# Audio_Input_Digitial_Mic.net
KiCad netlist of a schematic drawn in Altium Designer
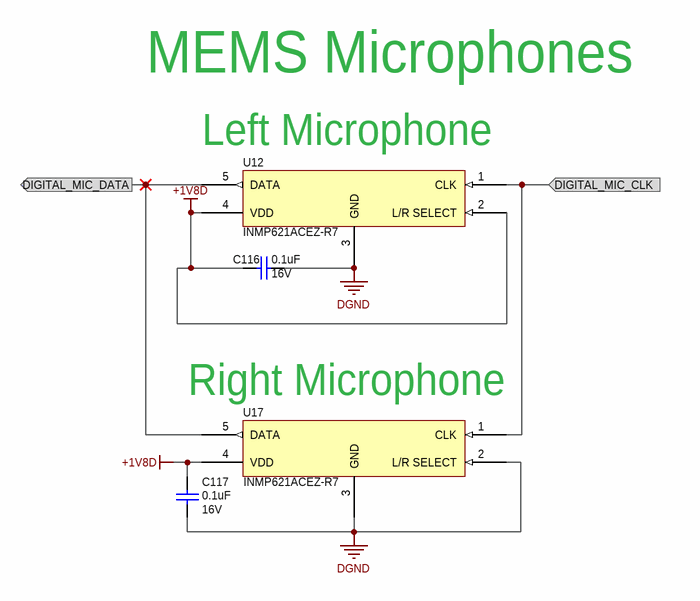
[diagram p0: Audio_Input_Digitial_Mic.SchDoc]

(export (version "E")
  (design (tool "Eeschema 10.0.6"))
  (components
    (comp (ref "C116")
      (value "CL10F104ZO8NNNC")
      (footprint "3-0603_L")
      (description "CAP CER 0.1UF 16V Y5V 0603")
      (fields
        (field (name "MANUFACTURER") "Samsung")
        (field (name "TOLERANCE") "80%")
        (field (name "VOLTAGE RATING") "16V")
        (field (name "CAPACITANCE") "0.1uF")
      )
      (libsource (lib "Schematic_Components_CD") (part "CL10F104ZO8NNNC"))
    )
    (comp (ref "C117")
      (value "CL10F104ZO8NNNC")
      (footprint "3-0603_L")
      (description "CAP CER 0.1UF 16V Y5V 0603")
      (fields
        (field (name "MANUFACTURER") "Samsung")
        (field (name "TOLERANCE") "80%")
        (field (name "VOLTAGE RATING") "16V")
        (field (name "CAPACITANCE") "0.1uF")
      )
      (libsource (lib "Schematic_Components_CD") (part "CL10F104ZO8NNNC"))
    )
    (comp (ref "U12")
      (value "INMP621")
      (footprint "INMP621")
      (fields
        (field (name "MANUFACTURER") "InvenSense")
        (field (name "MANUFACTURER PART NUMBER") "INMP621ACEZ-R7")
      )
      (libsource (lib "NIH_DE0_Nano_Daughter_Card_Library") (part "INMP621"))
    )
    (comp (ref "U17")
      (value "INMP621")
      (footprint "INMP621")
      (fields
        (field (name "MANUFACTURER") "InvenSense")
        (field (name "MANUFACTURER PART NUMBER") "INMP621ACEZ-R7")
      )
      (libsource (lib "NIH_DE0_Nano_Daughter_Card_Library") (part "INMP621"))
    )
  )
  (nets
    (net (code "1") (name "+1V8D") (class "Default")
      (node (ref "C116") (pin "2") (pinfunction "2_2") (pintype "passive"))
      (node (ref "C117") (pin "1") (pinfunction "1_1") (pintype "passive"))
      (node (ref "U12") (pin "2") (pinfunction "L/R_SELECT_2") (pintype "input"))
      (node (ref "U12") (pin "4") (pinfunction "VDD_4") (pintype "passive"))
      (node (ref "U17") (pin "4") (pinfunction "VDD_4") (pintype "passive"))
    )
    (net (code "2") (name "/DIGITAL_MIC_CLK") (class "Default")
      (node (ref "U12") (pin "1") (pinfunction "CLK_1") (pintype "input"))
      (node (ref "U17") (pin "1") (pinfunction "CLK_1") (pintype "input"))
    )
    (net (code "3") (name "/DIGITAL_MIC_DATA") (class "Default")
      (node (ref "U12") (pin "5") (pinfunction "DATA_5") (pintype "output"))
      (node (ref "U17") (pin "5") (pinfunction "DATA_5") (pintype "output"))
    )
    (net (code "4") (name "DGND") (class "Default")
      (node (ref "C116") (pin "1") (pinfunction "1_1") (pintype "passive"))
      (node (ref "C117") (pin "2") (pinfunction "2_2") (pintype "passive"))
      (node (ref "U12") (pin "3") (pinfunction "GND_3") (pintype "passive"))
      (node (ref "U17") (pin "2") (pinfunction "L/R_SELECT_2") (pintype "input"))
      (node (ref "U17") (pin "3") (pinfunction "GND_3") (pintype "passive"))
    )
  )
)
